# radio.net
KiCad netlist of a schematic drawn in Altium Designer
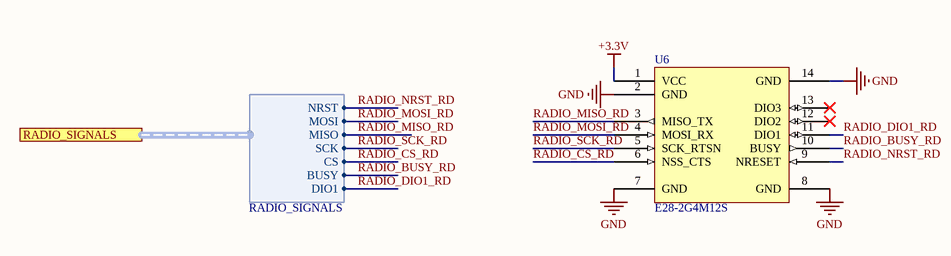
[diagram p0: radio.SchDoc]

(export (version "E")
  (design (tool "Eeschema 10.0.6"))
  (components
    (comp (ref "U6")
      (value "E28-2G4M12S")
      (footprint "PE28(2G4M12S)")
      (description "2.4GHz LoRa modules")
      (libsource (lib "IC_Library") (part "E28-2G4M12S"))
    )
  )
  (nets
    (net (code "2") (name "+3.3V") (class "Default")
      (node (ref "U6") (pin "1") (pinfunction "VCC_1") (pintype "passive"))
    )
    (net (code "3") (name "/RADIO_BUSY_RD") (class "Default")
      (node (ref "U6") (pin "10") (pinfunction "BUSY_10") (pintype "output"))
    )
    (net (code "4") (name "/RADIO_CS_RD") (class "Default")
      (node (ref "U6") (pin "6") (pinfunction "NSS_CTS_6") (pintype "input"))
    )
    (net (code "5") (name "/RADIO_DIO1_RD") (class "Default")
      (node (ref "U6") (pin "11") (pinfunction "DIO1_11") (pintype "bidirectional"))
    )
    (net (code "6") (name "/RADIO_MISO_RD") (class "Default")
      (node (ref "U6") (pin "3") (pinfunction "MISO_TX_3") (pintype "output"))
    )
    (net (code "7") (name "/RADIO_MOSI_RD") (class "Default")
      (node (ref "U6") (pin "4") (pinfunction "MOSI_RX_4") (pintype "input"))
    )
    (net (code "8") (name "/RADIO_NRST_RD") (class "Default")
      (node (ref "U6") (pin "9") (pinfunction "NRESET_9") (pintype "input"))
    )
    (net (code "9") (name "/RADIO_SCK_RD") (class "Default")
      (node (ref "U6") (pin "5") (pinfunction "SCK_RTSN_5") (pintype "input"))
    )
    (net (code "11") (name "GND") (class "Default")
      (node (ref "U6") (pin "14") (pinfunction "GND_14") (pintype "passive"))
      (node (ref "U6") (pin "2") (pinfunction "GND_2") (pintype "passive"))
      (node (ref "U6") (pin "7") (pinfunction "GND_7") (pintype "passive"))
      (node (ref "U6") (pin "8") (pinfunction "GND_8") (pintype "passive"))
    )
    (net (code "12") (name "unconnected-(U6-DIO2-Pad12)") (class "Default")
      (node (ref "U6") (pin "12") (pinfunction "DIO2_12") (pintype "bidirectional+no_connect"))
    )
    (net (code "13") (name "unconnected-(U6-DIO3-Pad13)") (class "Default")
      (node (ref "U6") (pin "13") (pinfunction "DIO3_13") (pintype "bidirectional+no_connect"))
    )
  )
)
